# koosh_sensor_top.net
KiCad netlist of a schematic drawn in Altium Designer
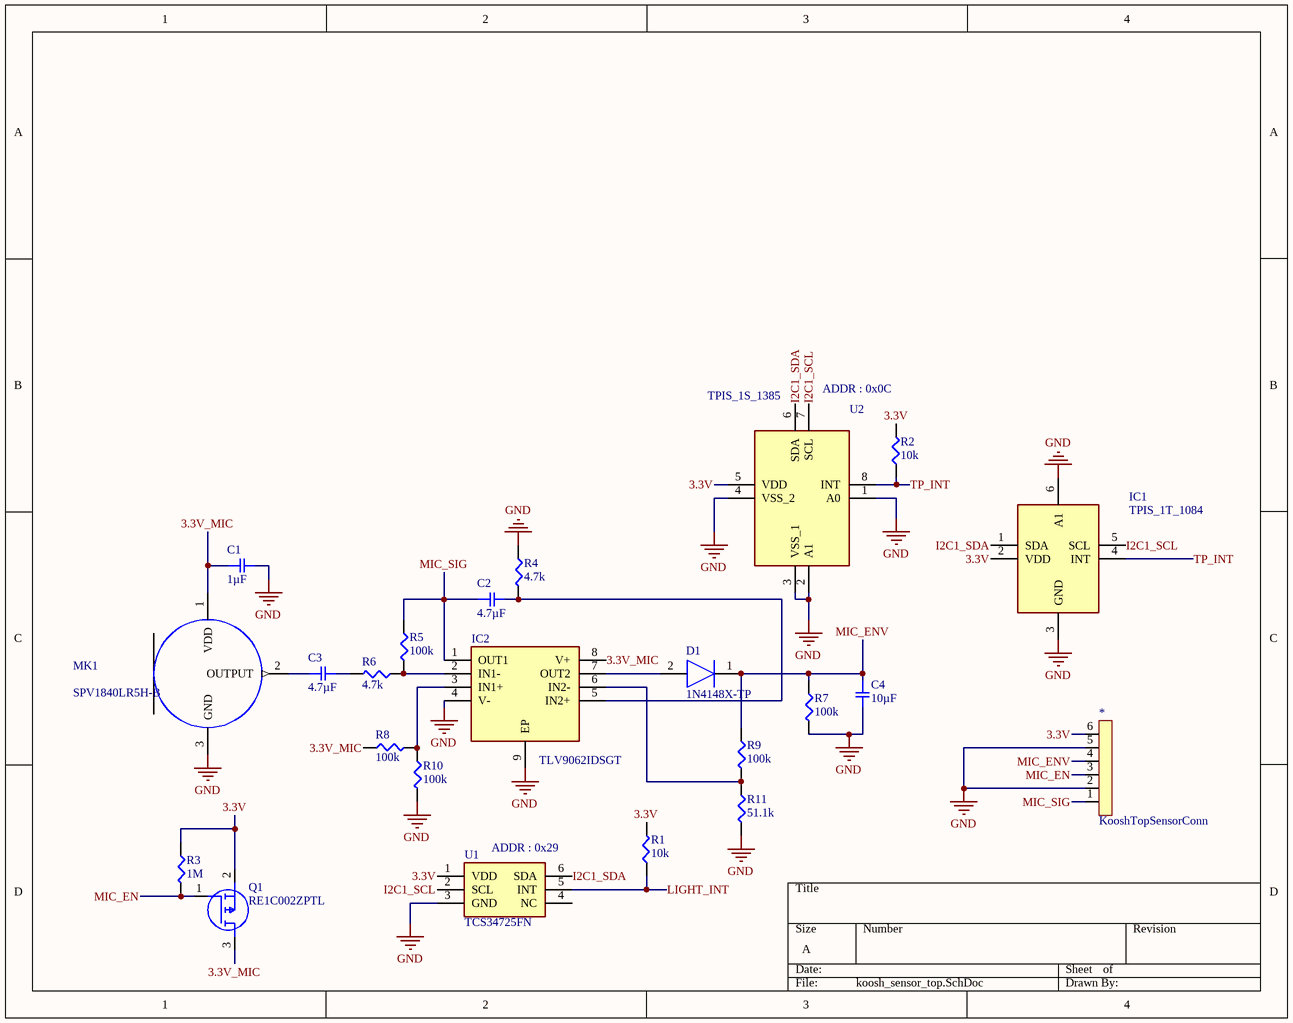
[diagram p0: koosh_sensor_top.SchDoc]

(export (version "E")
  (design (tool "Eeschema 10.0.6"))
  (components
    (comp (ref "*")
      (value "KooshTopSensorConn")
      (footprint "KooshTopBoardConn")
      (libsource (lib "schematic_components") (part "KooshTopSensorConn"))
    )
    (comp (ref "C1")
      (value "1µF")
      (footprint "Panasonic_ERJ_0402:SMD-0402-RES")
      (description "CAP CER 1UF 10V X7S 0402")
      (fields
        (field (name "DIGI-KEY PART NUMBER") "490-13409-1-ND")
        (field (name "PART NUMBER") "GCM155C71A105KE38D")
      )
      (libsource (lib "capacitor_murata_0402") (part "GCM155C71A105KE38D"))
    )
    (comp (ref "C2")
      (value "4.7µF")
      (footprint "SMD-0402C")
      (description "CAP CER 4.7UF 6.3V X5R 0402")
      (fields
        (field (name "DIGI-KEY PART NUMBER") "490-5915-1-ND")
        (field (name "PART NUMBER") "GRM155R60J475ME47D")
      )
      (libsource (lib "capacitor_murata_0402") (part "GRM155R60J475ME47D"))
    )
    (comp (ref "C3")
      (value "4.7µF")
      (footprint "SMD-0402C")
      (description "CAP CER 4.7UF 6.3V X5R 0402")
      (fields
        (field (name "DIGI-KEY PART NUMBER") "490-5915-1-ND")
        (field (name "PART NUMBER") "GRM155R60J475ME47D")
      )
      (libsource (lib "capacitor_murata_0402") (part "GRM155R60J475ME47D"))
    )
    (comp (ref "C4")
      (value "10µF")
      (footprint "CAPC1005X55N")
      (description "CAP CER 10UF 16V X7R 0402")
      (fields
        (field (name "DIGI-KEY PART NUMBER") "490-4759-1-ND")
        (field (name "PART NUMBER") "GCM155R71C104KA55D")
      )
      (libsource (lib "capacitor_murata_0402") (part "GCM155R71C104KA55D"))
    )
    (comp (ref "D1")
      (value "1N4148X-TP")
      (footprint "SamacSys:SODFL1608X70N")
      (description "Diode")
      (fields (field (name "MOUSER PART NUMBER") "833-1N4148X-TP"))
      (libsource (lib "*") (part "1N4148X-TP"))
    )
    (comp (ref "IC1")
      (value "TPIS_1T_1084")
      (footprint "SamacSys:TPIS1T1084")
      (description "Integrated Circuit")
      (fields (field (name "MANUFACTURER_PART_NUMBER") "TPIS 1T 1084"))
      (libsource (lib "*") (part "TPIS_1T_1084"))
    )
    (comp (ref "IC2")
      (value "TLV9062IDSGT")
      (footprint "SON50P200X200X80-9N")
      (description "Integrated Circuit")
      (fields (field (name "MOUSER PART NUMBER") "595-TLV9062IDSGT"))
      (libsource (lib "SamacSys") (part "TLV9062IDSGT"))
    )
    (comp (ref "MK1")
      (value "SPV1840LR5H-B")
      (footprint "*MIC_SPV1840LR5H-B")
      (description "Mic Mems Analog")
      (fields (field (name "MF") "Knowles"))
      (libsource (lib "schematic_components") (part "SPV1840LR5H-B"))
    )
    (comp (ref "Q1")
      (value "RE1C002ZPTL")
      (footprint "SamacSys:SOTFL50P160X85-3N")
      (description "MOSFET (P-Channel)")
      (fields
        (field (name "MOUSER PART NUMBER") "755-RE1C002ZPTL")
        (field (name "RS PART NUMBER") "1486960P")
      )
      (libsource (lib "*") (part "RE1C002ZPTL"))
    )
    (comp (ref "R1")
      (value "10k")
      (footprint "SMD-0402-RES")
      (description "RES SMD 10K OHM 5% 1/10W 0402")
      (fields (field (name "PART NUMBER") "ERJ-2GEJ103X") (field (name "DIGI-KEY PART NUMBER") "P10KJCT-ND"))
      (libsource (lib "Panasonic_ERJ_0402") (part "ERJ-2GEJ103X"))
    )
    (comp (ref "R2")
      (value "10k")
      (footprint "SMD-0402-RES")
      (description "RES SMD 10K OHM 5% 1/10W 0402")
      (fields (field (name "PART NUMBER") "ERJ-2GEJ103X") (field (name "DIGI-KEY PART NUMBER") "P10KJCT-ND"))
      (libsource (lib "Panasonic_ERJ_0402") (part "ERJ-2GEJ103X"))
    )
    (comp (ref "R3")
      (value "1M")
      (footprint "SMD-0402-RES")
      (description "RES SMD 1M OHM 5% 1/10W 0402")
      (fields (field (name "PART NUMBER") "ERJ-2GEJ105X") (field (name "DIGI-KEY PART NUMBER") "P1.0MJCT-ND"))
      (libsource (lib "Panasonic_ERJ_0402") (part "ERJ-2GEJ105X"))
    )
    (comp (ref "R4")
      (value "4.7k")
      (footprint "SMD-0402-RES")
      (description "RES SMD 4.7K OHM 5% 1/10W 0402")
      (fields (field (name "PART NUMBER") "ERJ-2GEJ103X") (field (name "DIGI-KEY PART NUMBER") "P10KJCT-ND"))
      (libsource (lib "Panasonic_ERJ_0402") (part "ERJ-2GEJ103X"))
    )
    (comp (ref "R5")
      (value "100k")
      (footprint "SMD-0402-RES")
      (description "RES SMD 100K OHM 5% 1/10W 0402")
      (fields (field (name "PART NUMBER") "ERJ-2GEJ103X") (field (name "DIGI-KEY PART NUMBER") "P10KJCT-ND"))
      (libsource (lib "Panasonic_ERJ_0402") (part "ERJ-2GEJ103X"))
    )
    (comp (ref "R6")
      (value "4.7k")
      (footprint "SMD-0402-RES")
      (description "RES SMD 4.7K OHM 5% 1/10W 0402")
      (fields (field (name "PART NUMBER") "ERJ-2GEJ103X") (field (name "DIGI-KEY PART NUMBER") "P10KJCT-ND"))
      (libsource (lib "Panasonic_ERJ_0402") (part "ERJ-2GEJ103X"))
    )
    (comp (ref "R7")
      (value "100k")
      (footprint "SMD-0402-RES")
      (description "RES SMD 100K OHM 5% 1/10W 0402")
      (fields (field (name "PART NUMBER") "ERJ-2GEJ103X") (field (name "DIGI-KEY PART NUMBER") "P10KJCT-ND"))
      (libsource (lib "Panasonic_ERJ_0402") (part "ERJ-2GEJ103X"))
    )
    (comp (ref "R8")
      (value "100k")
      (footprint "SMD-0402-RES")
      (description "RES SMD 100K OHM 5% 1/10W 0402")
      (fields (field (name "PART NUMBER") "ERJ-2GEJ103X") (field (name "DIGI-KEY PART NUMBER") "P10KJCT-ND"))
      (libsource (lib "Panasonic_ERJ_0402") (part "ERJ-2GEJ103X"))
    )
    (comp (ref "R9")
      (value "100k")
      (footprint "SMD-0402-RES")
      (description "RES SMD 100K OHM 5% 1/10W 0402")
      (fields (field (name "PART NUMBER") "ERJ-2GEJ103X") (field (name "DIGI-KEY PART NUMBER") "P10KJCT-ND"))
      (libsource (lib "Panasonic_ERJ_0402") (part "ERJ-2GEJ103X"))
    )
    (comp (ref "R10")
      (value "100k")
      (footprint "SMD-0402-RES")
      (description "RES SMD 100K OHM 5% 1/10W 0402")
      (fields (field (name "PART NUMBER") "ERJ-2GEJ103X") (field (name "DIGI-KEY PART NUMBER") "P10KJCT-ND"))
      (libsource (lib "Panasonic_ERJ_0402") (part "ERJ-2GEJ103X"))
    )
    (comp (ref "R11")
      (value "51.1k")
      (footprint "SMD-0402-RES")
      (description "RES SMD 51.1K OHM 5% 1/10W 0402")
      (fields (field (name "PART NUMBER") "ERJ-2GEJ103X") (field (name "DIGI-KEY PART NUMBER") "P10KJCT-ND"))
      (libsource (lib "Panasonic_ERJ_0402") (part "ERJ-2GEJ103X"))
    )
    (comp (ref "U1")
      (value "TCS34725FN")
      (footprint "SamacSys:FN_1")
      (description "Undefined or Miscellaneous")
      (fields (field (name "MOUSER PART NUMBER") "985-TCS34725FN") (field (name "RS PART NUMBER") "1024173P"))
      (libsource (lib "*") (part "TCS34725FN"))
    )
    (comp (ref "U2")
      (value "TPIS_1S_1385")
      (footprint "SamacSys:TPIS_1S_1385")
      (description "Undefined or Miscellaneous")
      (fields (field (name "MANUFACTURER_PART_NUMBER") "TPIS 1S 1385"))
      (libsource (lib "*") (part "TPIS_1S_1385"))
    )
  )
  (nets
    (net (code "1") (name "/3.3V") (class "Default")
      (node (ref "*") (pin "6") (pinfunction "1_6") (pintype "passive"))
      (node (ref "IC1") (pin "2") (pinfunction "VDD_2") (pintype "passive"))
      (node (ref "Q1") (pin "2") (pinfunction "S_2") (pintype "passive"))
      (node (ref "R1") (pin "2") (pinfunction "2_2") (pintype "passive"))
      (node (ref "R2") (pin "2") (pinfunction "2_2") (pintype "passive"))
      (node (ref "R3") (pin "1") (pinfunction "1_1") (pintype "passive"))
      (node (ref "U1") (pin "1") (pinfunction "VDD_1") (pintype "passive"))
      (node (ref "U2") (pin "5") (pinfunction "VDD_5") (pintype "passive"))
    )
    (net (code "2") (name "/3.3V_MIC") (class "Default")
      (node (ref "C1") (pin "1") (pinfunction "1_1") (pintype "passive"))
      (node (ref "IC2") (pin "8") (pinfunction "V+_8") (pintype "passive"))
      (node (ref "MK1") (pin "1") (pinfunction "VDD_1") (pintype "power_in"))
      (node (ref "Q1") (pin "3") (pinfunction "D_3") (pintype "passive"))
      (node (ref "R8") (pin "1") (pinfunction "1_1") (pintype "passive"))
    )
    (net (code "3") (name "/I2C1_SCL") (class "Default")
      (node (ref "IC1") (pin "5") (pinfunction "SCL_5") (pintype "passive"))
      (node (ref "U1") (pin "2") (pinfunction "SCL_2") (pintype "passive"))
      (node (ref "U2") (pin "7") (pinfunction "SCL_7") (pintype "passive"))
    )
    (net (code "4") (name "/I2C1_SDA") (class "Default")
      (node (ref "IC1") (pin "1") (pinfunction "SDA_1") (pintype "passive"))
      (node (ref "U1") (pin "6") (pinfunction "SDA_6") (pintype "passive"))
      (node (ref "U2") (pin "6") (pinfunction "SDA_6") (pintype "passive"))
    )
    (net (code "5") (name "/LIGHT_INT") (class "Default")
      (node (ref "R1") (pin "1") (pinfunction "1_1") (pintype "passive"))
      (node (ref "U1") (pin "5") (pinfunction "INT_5") (pintype "passive"))
    )
    (net (code "6") (name "/MIC_EN") (class "Default")
      (node (ref "*") (pin "3") (pinfunction "3_3") (pintype "passive"))
      (node (ref "Q1") (pin "1") (pinfunction "G_1") (pintype "passive"))
      (node (ref "R3") (pin "2") (pinfunction "2_2") (pintype "passive"))
    )
    (net (code "7") (name "/MIC_ENV") (class "Default")
      (node (ref "*") (pin "4") (pinfunction "4_4") (pintype "passive"))
      (node (ref "C4") (pin "1") (pinfunction "1_1") (pintype "passive"))
      (node (ref "D1") (pin "1") (pinfunction "K_1") (pintype "passive"))
      (node (ref "R7") (pin "1") (pinfunction "1_1") (pintype "passive"))
      (node (ref "R9") (pin "1") (pinfunction "1_1") (pintype "passive"))
    )
    (net (code "8") (name "/MIC_SIG") (class "Default")
      (node (ref "*") (pin "1") (pinfunction "1_1") (pintype "passive"))
      (node (ref "C2") (pin "1") (pinfunction "1_1") (pintype "passive"))
      (node (ref "IC2") (pin "1") (pinfunction "OUT1_1") (pintype "passive"))
      (node (ref "R5") (pin "1") (pinfunction "1_1") (pintype "passive"))
    )
    (net (code "9") (name "/TP_INT") (class "Default")
      (node (ref "IC1") (pin "4") (pinfunction "INT_4") (pintype "passive"))
      (node (ref "R2") (pin "1") (pinfunction "1_1") (pintype "passive"))
      (node (ref "U2") (pin "8") (pinfunction "INT_8") (pintype "passive"))
    )
    (net (code "10") (name "GND") (class "Default")
      (node (ref "*") (pin "2") (pinfunction "2_2") (pintype "passive"))
      (node (ref "*") (pin "5") (pinfunction "5_5") (pintype "passive"))
      (node (ref "C1") (pin "2") (pinfunction "2_2") (pintype "passive"))
      (node (ref "C4") (pin "2") (pinfunction "2_2") (pintype "passive"))
      (node (ref "IC1") (pin "3") (pinfunction "GND_3") (pintype "passive"))
      (node (ref "IC1") (pin "6") (pinfunction "A1_6") (pintype "passive"))
      (node (ref "IC2") (pin "4") (pinfunction "V-_4") (pintype "passive"))
      (node (ref "IC2") (pin "9") (pinfunction "EP_9") (pintype "passive"))
      (node (ref "MK1") (pin "3") (pinfunction "GND_3") (pintype "passive"))
      (node (ref "R10") (pin "2") (pinfunction "2_2") (pintype "passive"))
      (node (ref "R11") (pin "2") (pinfunction "2_2") (pintype "passive"))
      (node (ref "R4") (pin "1") (pinfunction "1_1") (pintype "passive"))
      (node (ref "R7") (pin "2") (pinfunction "2_2") (pintype "passive"))
      (node (ref "U1") (pin "3") (pinfunction "GND_3") (pintype "passive"))
      (node (ref "U2") (pin "1") (pinfunction "A0_1") (pintype "passive"))
      (node (ref "U2") (pin "2") (pinfunction "A1_2") (pintype "passive"))
      (node (ref "U2") (pin "3") (pinfunction "VSS_1_3") (pintype "passive"))
      (node (ref "U2") (pin "4") (pinfunction "VSS_2_4") (pintype "passive"))
    )
    (net (code "11") (name "Net-(C3-Pad2)") (class "Default")
      (node (ref "C3") (pin "2") (pinfunction "2_2") (pintype "passive"))
      (node (ref "R6") (pin "2") (pinfunction "2_2") (pintype "passive"))
    )
    (net (code "12") (name "Net-(D1-A)") (class "Default")
      (node (ref "D1") (pin "2") (pinfunction "A_2") (pintype "passive"))
      (node (ref "IC2") (pin "7") (pinfunction "OUT2_7") (pintype "passive"))
    )
    (net (code "13") (name "Net-(IC2-IN1+)") (class "Default")
      (node (ref "IC2") (pin "3") (pinfunction "IN1+_3") (pintype "passive"))
      (node (ref "R10") (pin "1") (pinfunction "1_1") (pintype "passive"))
      (node (ref "R8") (pin "2") (pinfunction "2_2") (pintype "passive"))
    )
    (net (code "14") (name "Net-(IC2-IN1-)") (class "Default")
      (node (ref "IC2") (pin "2") (pinfunction "IN1-_2") (pintype "passive"))
      (node (ref "R5") (pin "2") (pinfunction "2_2") (pintype "passive"))
      (node (ref "R6") (pin "1") (pinfunction "1_1") (pintype "passive"))
    )
    (net (code "15") (name "Net-(IC2-IN2+)") (class "Default")
      (node (ref "C2") (pin "2") (pinfunction "2_2") (pintype "passive"))
      (node (ref "IC2") (pin "5") (pinfunction "IN2+_5") (pintype "passive"))
      (node (ref "R4") (pin "2") (pinfunction "2_2") (pintype "passive"))
    )
    (net (code "16") (name "Net-(IC2-IN2-)") (class "Default")
      (node (ref "IC2") (pin "6") (pinfunction "IN2-_6") (pintype "passive"))
      (node (ref "R11") (pin "1") (pinfunction "1_1") (pintype "passive"))
      (node (ref "R9") (pin "2") (pinfunction "2_2") (pintype "passive"))
    )
    (net (code "17") (name "Net-(MK1-OUTPUT)") (class "Default")
      (node (ref "C3") (pin "1") (pinfunction "1_1") (pintype "passive"))
      (node (ref "MK1") (pin "2") (pinfunction "OUTPUT_2") (pintype "output"))
    )
    (net (code "18") (name "unconnected-(U1-NC-Pad4)") (class "Default")
      (node (ref "U1") (pin "4") (pinfunction "NC_4") (pintype "passive"))
    )
  )
)
